# SOIC_TSSOP-16_600mil_DIP.net
KiCad netlist of a schematic drawn in EAGLE
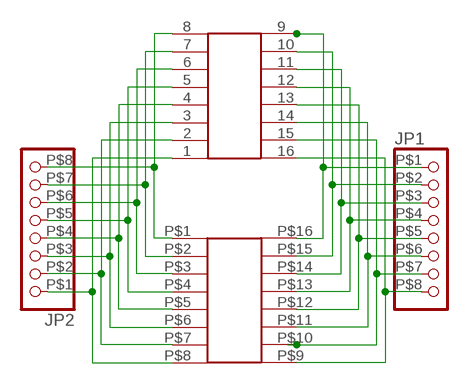
[diagram p0: schematic, sheet 1]

(export (version "E")
  (design (tool "Eeschema 10.0.6"))
  (components
    (comp (ref "JP1")
      (value "PINHD-1X8THIN")
      (footprint "eagle-import:HEADER1X8")
      (libsource (lib "eagle-import") (part "PINHD-1X8THIN"))
    )
    (comp (ref "JP2")
      (value "PINHD-1X8THIN")
      (footprint "eagle-import:HEADER1X8")
      (libsource (lib "eagle-import") (part "PINHD-1X8THIN"))
    )
    (comp (ref "U$1")
      (value "SMD-16SOIC")
      (footprint "eagle-import:SO-16NMW")
      (libsource (lib "eagle-import") (part "SMD-16SOIC"))
    )
    (comp (ref "U$2")
      (value "SMD-16TSSOP")
      (footprint "eagle-import:TSSOP-16NM")
      (libsource (lib "eagle-import") (part "SMD-16TSSOP"))
    )
  )
  (nets
    (net (code "1") (name "Net-(JP1-1)") (class "Default")
      (node (ref "JP1") (pin "P$1") (pinfunction "1_P$1") (pintype "passive"))
      (node (ref "U$1") (pin "P$16") (pinfunction "P$16_P$16") (pintype "bidirectional"))
      (node (ref "U$2") (pin "9") (pinfunction "P$9_9") (pintype "bidirectional"))
    )
    (net (code "2") (name "Net-(JP1-2)") (class "Default")
      (node (ref "JP1") (pin "P$2") (pinfunction "2_P$2") (pintype "passive"))
      (node (ref "U$1") (pin "P$15") (pinfunction "P$15_P$15") (pintype "bidirectional"))
      (node (ref "U$2") (pin "10") (pinfunction "P$10_10") (pintype "bidirectional"))
    )
    (net (code "3") (name "Net-(JP1-3)") (class "Default")
      (node (ref "JP1") (pin "P$3") (pinfunction "3_P$3") (pintype "passive"))
      (node (ref "U$1") (pin "P$14") (pinfunction "P$14_P$14") (pintype "bidirectional"))
      (node (ref "U$2") (pin "11") (pinfunction "P$11_11") (pintype "bidirectional"))
    )
    (net (code "4") (name "Net-(JP1-4)") (class "Default")
      (node (ref "JP1") (pin "P$4") (pinfunction "4_P$4") (pintype "passive"))
      (node (ref "U$1") (pin "P$13") (pinfunction "P$13_P$13") (pintype "bidirectional"))
      (node (ref "U$2") (pin "12") (pinfunction "P$12_12") (pintype "bidirectional"))
    )
    (net (code "5") (name "Net-(JP1-5)") (class "Default")
      (node (ref "JP1") (pin "P$5") (pinfunction "5_P$5") (pintype "passive"))
      (node (ref "U$1") (pin "P$12") (pinfunction "P$12_P$12") (pintype "bidirectional"))
      (node (ref "U$2") (pin "13") (pinfunction "P$13_13") (pintype "bidirectional"))
    )
    (net (code "6") (name "Net-(JP1-6)") (class "Default")
      (node (ref "JP1") (pin "P$6") (pinfunction "6_P$6") (pintype "passive"))
      (node (ref "U$1") (pin "P$11") (pinfunction "P$11_P$11") (pintype "bidirectional"))
      (node (ref "U$2") (pin "14") (pinfunction "P$14_14") (pintype "bidirectional"))
    )
    (net (code "7") (name "Net-(JP1-7)") (class "Default")
      (node (ref "JP1") (pin "P$7") (pinfunction "7_P$7") (pintype "passive"))
      (node (ref "U$1") (pin "P$10") (pinfunction "P$10_P$10") (pintype "bidirectional"))
      (node (ref "U$2") (pin "15") (pinfunction "P$15_15") (pintype "bidirectional"))
    )
    (net (code "8") (name "Net-(JP1-8)") (class "Default")
      (node (ref "JP1") (pin "P$8") (pinfunction "8_P$8") (pintype "passive"))
      (node (ref "U$1") (pin "P$9") (pinfunction "P$9_P$9") (pintype "bidirectional"))
      (node (ref "U$2") (pin "16") (pinfunction "P$16_16") (pintype "bidirectional"))
    )
    (net (code "9") (name "Net-(JP2-1)") (class "Default")
      (node (ref "JP2") (pin "P$1") (pinfunction "1_P$1") (pintype "passive"))
      (node (ref "U$1") (pin "P$8") (pinfunction "P$8_P$8") (pintype "bidirectional"))
      (node (ref "U$2") (pin "1") (pinfunction "P$1_1") (pintype "bidirectional"))
    )
    (net (code "10") (name "Net-(JP2-2)") (class "Default")
      (node (ref "JP2") (pin "P$2") (pinfunction "2_P$2") (pintype "passive"))
      (node (ref "U$1") (pin "P$7") (pinfunction "P$7_P$7") (pintype "bidirectional"))
      (node (ref "U$2") (pin "2") (pinfunction "P$2_2") (pintype "bidirectional"))
    )
    (net (code "11") (name "Net-(JP2-3)") (class "Default")
      (node (ref "JP2") (pin "P$3") (pinfunction "3_P$3") (pintype "passive"))
      (node (ref "U$1") (pin "P$6") (pinfunction "P$6_P$6") (pintype "bidirectional"))
      (node (ref "U$2") (pin "3") (pinfunction "P$3_3") (pintype "bidirectional"))
    )
    (net (code "12") (name "Net-(JP2-4)") (class "Default")
      (node (ref "JP2") (pin "P$4") (pinfunction "4_P$4") (pintype "passive"))
      (node (ref "U$1") (pin "P$5") (pinfunction "P$5_P$5") (pintype "bidirectional"))
      (node (ref "U$2") (pin "4") (pinfunction "P$4_4") (pintype "bidirectional"))
    )
    (net (code "13") (name "Net-(JP2-5)") (class "Default")
      (node (ref "JP2") (pin "P$5") (pinfunction "5_P$5") (pintype "passive"))
      (node (ref "U$1") (pin "P$4") (pinfunction "P$4_P$4") (pintype "bidirectional"))
      (node (ref "U$2") (pin "5") (pinfunction "P$5_5") (pintype "bidirectional"))
    )
    (net (code "14") (name "Net-(JP2-6)") (class "Default")
      (node (ref "JP2") (pin "P$6") (pinfunction "6_P$6") (pintype "passive"))
      (node (ref "U$1") (pin "P$3") (pinfunction "P$3_P$3") (pintype "bidirectional"))
      (node (ref "U$2") (pin "6") (pinfunction "P$6_6") (pintype "bidirectional"))
    )
    (net (code "15") (name "Net-(JP2-7)") (class "Default")
      (node (ref "JP2") (pin "P$7") (pinfunction "7_P$7") (pintype "passive"))
      (node (ref "U$1") (pin "P$2") (pinfunction "P$2_P$2") (pintype "bidirectional"))
      (node (ref "U$2") (pin "7") (pinfunction "P$7_7") (pintype "bidirectional"))
    )
    (net (code "16") (name "Net-(JP2-8)") (class "Default")
      (node (ref "JP2") (pin "P$8") (pinfunction "8_P$8") (pintype "passive"))
      (node (ref "U$1") (pin "P$1") (pinfunction "P$1_P$1") (pintype "bidirectional"))
      (node (ref "U$2") (pin "8") (pinfunction "P$8_8") (pintype "bidirectional"))
    )
  )
)
